# lab5_v1.net
KiCad netlist of a schematic drawn in EAGLE
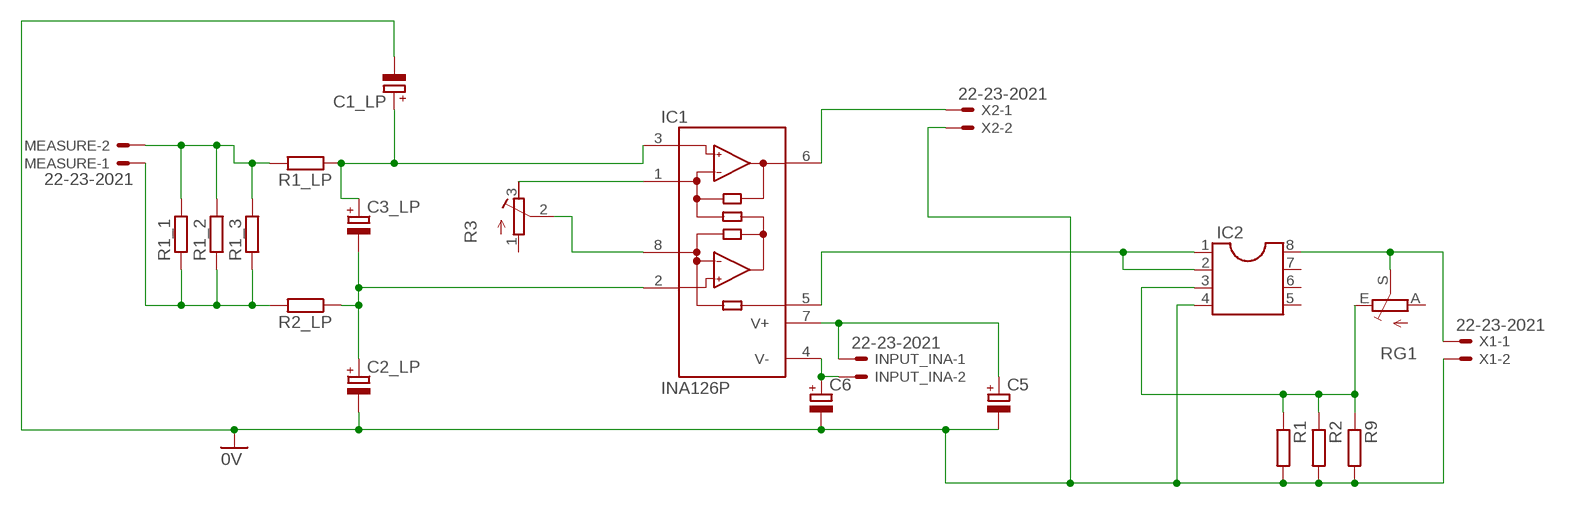
[diagram p0: schematic, sheet 1]

(export (version "E")
  (design (tool "Eeschema 10.0.6"))
  (components
    (comp (ref "C1_LP")
      (value "CPOL-EUE5-10.5")
      (footprint "eagle-import:E5-10,5")
      (libsource (lib "eagle-import") (part "CPOL-EUE5-10.5"))
    )
    (comp (ref "C2_LP")
      (value "CPOL-EUE5-10.5")
      (footprint "eagle-import:E5-10,5")
      (libsource (lib "eagle-import") (part "CPOL-EUE5-10.5"))
    )
    (comp (ref "C3_LP")
      (value "CPOL-EUE5-10.5")
      (footprint "eagle-import:E5-10,5")
      (libsource (lib "eagle-import") (part "CPOL-EUE5-10.5"))
    )
    (comp (ref "C5")
      (value "CPOL-EUE5-10.5")
      (footprint "eagle-import:E5-10,5")
      (libsource (lib "eagle-import") (part "CPOL-EUE5-10.5"))
    )
    (comp (ref "C6")
      (value "CPOL-EUE5-10.5")
      (footprint "eagle-import:E5-10,5")
      (libsource (lib "eagle-import") (part "CPOL-EUE5-10.5"))
    )
    (comp (ref "IC1")
      (value "INA126P")
      (footprint "eagle-import:DIL08")
      (fields (field (name "MF") "TEXAS INSTRUMENT CONNECTORS"))
      (libsource (lib "eagle-import") (part "INA126P"))
    )
    (comp (ref "IC2")
      (value "DIL8")
      (footprint "eagle-import:DIL08")
      (libsource (lib "eagle-import") (part "DIL8"))
    )
    (comp (ref "INPUT_INA")
      (value "22-23-2021")
      (footprint "eagle-import:22-23-2021")
      (fields (field (name "MF") "MOLEX"))
      (libsource (lib "eagle-import") (part "22-23-2021"))
    )
    (comp (ref "MEASURE")
      (value "22-23-2021")
      (footprint "eagle-import:22-23-2021")
      (fields (field (name "MF") "MOLEX"))
      (libsource (lib "eagle-import") (part "22-23-2021"))
    )
    (comp (ref "R1")
      (value "R-EU_0207/7")
      (footprint "eagle-import:0207_7")
      (libsource (lib "eagle-import") (part "R-EU_0207/7"))
    )
    (comp (ref "R1_1")
      (value "R-EU_0617/22")
      (footprint "eagle-import:0617_22")
      (libsource (lib "eagle-import") (part "R-EU_0617/22"))
    )
    (comp (ref "R1_2")
      (value "R-EU_0617/22")
      (footprint "eagle-import:0617_22")
      (libsource (lib "eagle-import") (part "R-EU_0617/22"))
    )
    (comp (ref "R1_3")
      (value "R-EU_0617/22")
      (footprint "eagle-import:0617_22")
      (libsource (lib "eagle-import") (part "R-EU_0617/22"))
    )
    (comp (ref "R1_LP")
      (value "R-EU_0207/7")
      (footprint "eagle-import:0207_7")
      (libsource (lib "eagle-import") (part "R-EU_0207/7"))
    )
    (comp (ref "R2")
      (value "R-EU_0207/7")
      (footprint "eagle-import:0207_7")
      (libsource (lib "eagle-import") (part "R-EU_0207/7"))
    )
    (comp (ref "R2_LP")
      (value "R-EU_0207/7")
      (footprint "eagle-import:0207_7")
      (libsource (lib "eagle-import") (part "R-EU_0207/7"))
    )
    (comp (ref "R3")
      (value "R-TRIMM64X")
      (footprint "eagle-import:RTRIM64X")
      (libsource (lib "eagle-import") (part "R-TRIMM64X"))
    )
    (comp (ref "R9")
      (value "R-EU_0207/7")
      (footprint "eagle-import:0207_7")
      (libsource (lib "eagle-import") (part "R-EU_0207/7"))
    )
    (comp (ref "RG1")
      (value "TRIM_EU-B25P")
      (footprint "eagle-import:B25P")
      (libsource (lib "eagle-import") (part "TRIM_EU-B25P"))
    )
    (comp (ref "X1")
      (value "22-23-2021")
      (footprint "eagle-import:22-23-2021")
      (fields (field (name "MF") "MOLEX"))
      (libsource (lib "eagle-import") (part "22-23-2021"))
    )
    (comp (ref "X2")
      (value "22-23-2021")
      (footprint "eagle-import:22-23-2021")
      (fields (field (name "MF") "MOLEX"))
      (libsource (lib "eagle-import") (part "22-23-2021"))
    )
  )
  (nets
    (net (code "1") (name "0V") (class "Default")
      (node (ref "C1_LP") (pin "-") (pinfunction "-_-") (pintype "passive"))
      (node (ref "C2_LP") (pin "-") (pinfunction "-_-") (pintype "passive"))
      (node (ref "C5") (pin "-") (pinfunction "-_-") (pintype "passive"))
      (node (ref "C6") (pin "-") (pinfunction "-_-") (pintype "passive"))
      (node (ref "IC2") (pin "4") (pinfunction "4_4") (pintype "passive"))
      (node (ref "R1") (pin "2") (pinfunction "2_2") (pintype "passive"))
      (node (ref "R2") (pin "2") (pinfunction "2_2") (pintype "passive"))
      (node (ref "R9") (pin "2") (pinfunction "2_2") (pintype "passive"))
      (node (ref "X1") (pin "2") (pinfunction "S_2") (pintype "passive"))
      (node (ref "X2") (pin "2") (pinfunction "S_2") (pintype "passive"))
    )
    (net (code "2") (name "Net-(IC1-+IN)") (class "Default")
      (node (ref "C1_LP") (pin "+") (pinfunction "+_+") (pintype "passive"))
      (node (ref "C3_LP") (pin "+") (pinfunction "+_+") (pintype "passive"))
      (node (ref "IC1") (pin "3") (pinfunction "+IN_3") (pintype "input"))
      (node (ref "R1_LP") (pin "1") (pinfunction "1_1") (pintype "passive"))
    )
    (net (code "3") (name "Net-(IC1--IN)") (class "Default")
      (node (ref "C2_LP") (pin "+") (pinfunction "+_+") (pintype "passive"))
      (node (ref "C3_LP") (pin "-") (pinfunction "-_-") (pintype "passive"))
      (node (ref "IC1") (pin "2") (pinfunction "-IN_2") (pintype "input"))
      (node (ref "R2_LP") (pin "1") (pinfunction "1_1") (pintype "passive"))
    )
    (net (code "4") (name "Net-(IC1-OUT)") (class "Default")
      (node (ref "IC1") (pin "6") (pinfunction "OUT_6") (pintype "output"))
      (node (ref "X2") (pin "1") (pinfunction "S_1") (pintype "passive"))
    )
    (net (code "5") (name "Net-(IC1-REF)") (class "Default")
      (node (ref "IC1") (pin "5") (pinfunction "REF_5") (pintype "passive"))
      (node (ref "IC2") (pin "1") (pinfunction "1_1") (pintype "passive"))
      (node (ref "IC2") (pin "2") (pinfunction "2_2") (pintype "passive"))
    )
    (net (code "6") (name "Net-(IC1-V+)") (class "Default")
      (node (ref "C5") (pin "+") (pinfunction "+_+") (pintype "passive"))
      (node (ref "IC1") (pin "7") (pinfunction "V+_7") (pintype "power_in"))
      (node (ref "INPUT_INA") (pin "1") (pinfunction "S_1") (pintype "passive"))
    )
    (net (code "7") (name "Net-(IC1-V-)") (class "Default")
      (node (ref "C6") (pin "+") (pinfunction "+_+") (pintype "passive"))
      (node (ref "IC1") (pin "4") (pinfunction "V-_4") (pintype "power_in"))
      (node (ref "INPUT_INA") (pin "2") (pinfunction "S_2") (pintype "passive"))
    )
    (net (code "8") (name "Net-(IC2-Pad3)") (class "Default")
      (node (ref "IC2") (pin "3") (pinfunction "3_3") (pintype "passive"))
      (node (ref "R1") (pin "1") (pinfunction "1_1") (pintype "passive"))
      (node (ref "R2") (pin "1") (pinfunction "1_1") (pintype "passive"))
      (node (ref "R9") (pin "1") (pinfunction "1_1") (pintype "passive"))
      (node (ref "RG1") (pin "E") (pinfunction "E_E") (pintype "passive"))
    )
    (net (code "9") (name "Net-(MEASUREA-S)") (class "Default")
      (node (ref "MEASURE") (pin "1") (pinfunction "S_1") (pintype "passive"))
      (node (ref "R1_1") (pin "1") (pinfunction "1_1") (pintype "passive"))
      (node (ref "R1_2") (pin "1") (pinfunction "1_1") (pintype "passive"))
      (node (ref "R1_3") (pin "1") (pinfunction "1_1") (pintype "passive"))
      (node (ref "R2_LP") (pin "2") (pinfunction "2_2") (pintype "passive"))
    )
    (net (code "10") (name "Net-(MEASUREB-S)") (class "Default")
      (node (ref "MEASURE") (pin "2") (pinfunction "S_2") (pintype "passive"))
      (node (ref "R1_1") (pin "2") (pinfunction "2_2") (pintype "passive"))
      (node (ref "R1_2") (pin "2") (pinfunction "2_2") (pintype "passive"))
      (node (ref "R1_3") (pin "2") (pinfunction "2_2") (pintype "passive"))
      (node (ref "R1_LP") (pin "2") (pinfunction "2_2") (pintype "passive"))
    )
    (net (code "11") (name "Net-(R3-A)") (class "Default")
      (node (ref "IC1") (pin "1") (pinfunction "RG_1") (pintype "passive"))
      (node (ref "R3") (pin "3") (pinfunction "A_3") (pintype "passive"))
    )
    (net (code "12") (name "Net-(R3-S)") (class "Default")
      (node (ref "IC1") (pin "8") (pinfunction "RG_8") (pintype "passive"))
      (node (ref "R3") (pin "2") (pinfunction "S_2") (pintype "passive"))
    )
    (net (code "13") (name "Net-(X1A-S)") (class "Default")
      (node (ref "IC2") (pin "8") (pinfunction "8_8") (pintype "passive"))
      (node (ref "RG1") (pin "S") (pinfunction "S_S") (pintype "passive"))
      (node (ref "X1") (pin "1") (pinfunction "S_1") (pintype "passive"))
    )
    (net (code "14") (name "unconnected-(IC2-Pad5)") (class "Default")
      (node (ref "IC2") (pin "5") (pinfunction "5_5") (pintype "passive"))
    )
    (net (code "15") (name "unconnected-(IC2-Pad6)") (class "Default")
      (node (ref "IC2") (pin "6") (pinfunction "6_6") (pintype "passive"))
    )
    (net (code "16") (name "unconnected-(IC2-Pad7)") (class "Default")
      (node (ref "IC2") (pin "7") (pinfunction "7_7") (pintype "passive"))
    )
    (net (code "17") (name "unconnected-(R3-E-Pad1)") (class "Default")
      (node (ref "R3") (pin "1") (pinfunction "E_1") (pintype "passive"))
    )
    (net (code "18") (name "unconnected-(RG1-PadA)") (class "Default")
      (node (ref "RG1") (pin "A") (pinfunction "A_A") (pintype "passive"))
    )
  )
)
